# Digital_IO.net
KiCad netlist of a schematic drawn in Altium Designer
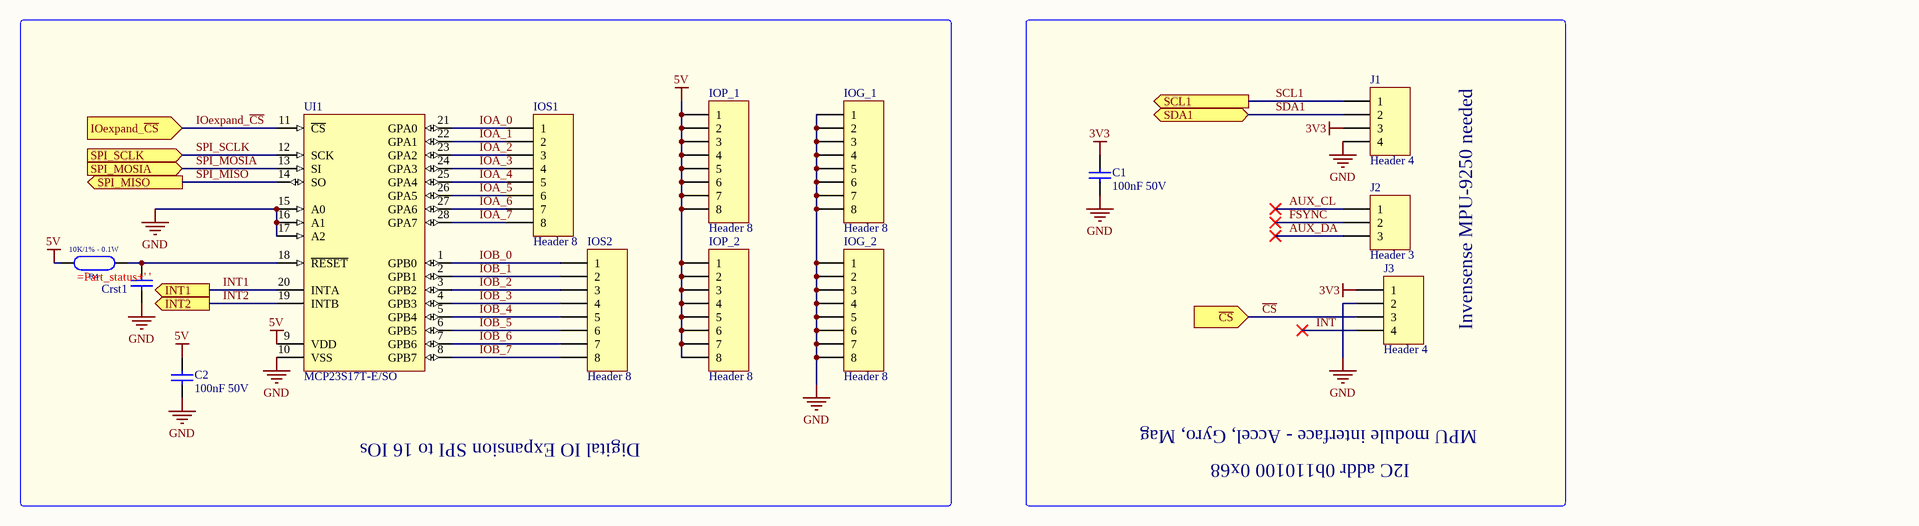
[diagram p0: Digital_IO.SchDoc]

(export (version "E")
  (design (tool "Eeschema 10.0.6"))
  (components
    (comp (ref "C1")
      (value "100nF 50V")
      (footprint "0603C_L")
      (fields
        (field (name "MANUFACTURER") "Yageo")
        (field (name "MANUFACTURER PART NUMBER") "CC0603ZRY5V9BB104")
        (field (name "TOLERANCE") "-20%, +80%")
      )
      (libsource (lib "WCT") (part "Cap101nF_50V_0603"))
    )
    (comp (ref "C2")
      (value "100nF 50V")
      (footprint "0603C_L")
      (fields
        (field (name "MANUFACTURER") "Yageo")
        (field (name "MANUFACTURER PART NUMBER") "CC0603ZRY5V9BB104")
        (field (name "TOLERANCE") "-20%, +80%")
      )
      (libsource (lib "WCT") (part "Cap101nF_50V_0603"))
    )
    (comp (ref "Crst1")
      (value "100nF 50V")
      (footprint "0603C_L")
      (fields
        (field (name "MANUFACTURER") "Yageo")
        (field (name "MANUFACTURER PART NUMBER") "CC0603ZRY5V9BB104")
        (field (name "TOLERANCE") "-20%, +80%")
      )
      (libsource (lib "WCT") (part "Cap100nF_50V_0603"))
    )
    (comp (ref "IOG_1")
      (value "Header 8")
      (footprint "HDR1X8")
      (description "Header, 8-Pin")
      (fields (field (name "PUBLISHER") "Altium Limited"))
      (libsource (lib "Miscellaneous Connectors") (part "Header 8"))
    )
    (comp (ref "IOG_2")
      (value "Header 8")
      (footprint "HDR1X8")
      (description "Header, 8-Pin")
      (fields (field (name "PUBLISHER") "Altium Limited"))
      (libsource (lib "Miscellaneous Connectors") (part "Header 8"))
    )
    (comp (ref "IOP_1")
      (value "Header 8")
      (footprint "HDR1X8")
      (description "Header, 8-Pin")
      (fields (field (name "PUBLISHER") "Altium Limited"))
      (libsource (lib "Miscellaneous Connectors") (part "Header 8"))
    )
    (comp (ref "IOP_2")
      (value "Header 8")
      (footprint "HDR1X8")
      (description "Header, 8-Pin")
      (fields (field (name "PUBLISHER") "Altium Limited"))
      (libsource (lib "Miscellaneous Connectors") (part "Header 8"))
    )
    (comp (ref "IOS1")
      (value "Header 8")
      (footprint "HDR1X8")
      (description "Header, 8-Pin")
      (fields (field (name "PUBLISHER") "Altium Limited"))
      (libsource (lib "Miscellaneous Connectors") (part "Header 8"))
    )
    (comp (ref "IOS2")
      (value "Header 8")
      (footprint "HDR1X8")
      (description "Header, 8-Pin")
      (fields (field (name "PUBLISHER") "Altium Limited"))
      (libsource (lib "Miscellaneous Connectors") (part "Header 8"))
    )
    (comp (ref "J1")
      (value "Header 4")
      (footprint "HDR1X4")
      (description "Header, 4-Pin")
      (fields (field (name "PUBLISHER") "Altium Limited"))
      (libsource (lib "Miscellaneous Connectors") (part "Header 4"))
    )
    (comp (ref "J2")
      (value "Header 3")
      (footprint "HDR1X3")
      (description "Header, 3-Pin")
      (fields (field (name "PUBLISHER") "Altium Limited"))
      (libsource (lib "Miscellaneous Connectors") (part "Header 3"))
    )
    (comp (ref "J3")
      (value "Header 4")
      (footprint "HDR1X4")
      (description "Header, 4-Pin")
      (fields (field (name "PUBLISHER") "Altium Limited"))
      (libsource (lib "Miscellaneous Connectors") (part "Header 4"))
    )
    (comp (ref "R4")
      (value "10K/1% - 0.1W")
      (footprint "R0603")
      (description "Resistor 10K ±1% 0.1W 0603")
      (fields (field (name "TOLERANCE") "±1%") (field (name "POWER") "0.1W"))
      (libsource (lib "EDS_Hardware_gitLIB_Perto") (part "Resistor"))
    )
    (comp (ref "UI1")
      (value "MCP23S17T-E/SO")
      (footprint "SOIC-SO28_L")
      (description "16-Bit I/O Expander with Serial Interface, 28-Pin SOIC, Extended Temperature, Tape and Reel")
      (libsource (lib "Altium Content Vault") (part "CMP-0186-00131-2"))
    )
  )
  (nets
    (net (code "1") (name "/AUX_CL") (class "Default")
      (node (ref "J2") (pin "1") (pinfunction "1_1") (pintype "passive+no_connect"))
    )
    (net (code "2") (name "/AUX_DA") (class "Default")
      (node (ref "J2") (pin "3") (pinfunction "3_3") (pintype "passive+no_connect"))
    )
    (net (code "3") (name "/FSYNC") (class "Default")
      (node (ref "J2") (pin "2") (pinfunction "2_2") (pintype "passive+no_connect"))
    )
    (net (code "4") (name "/INT") (class "Default")
      (node (ref "J3") (pin "4") (pinfunction "4_4") (pintype "passive+no_connect"))
    )
    (net (code "5") (name "/INT1") (class "Default")
      (node (ref "UI1") (pin "20") (pinfunction "INTA_20") (pintype "open_collector"))
    )
    (net (code "6") (name "/INT2") (class "Default")
      (node (ref "UI1") (pin "19") (pinfunction "INTB_19") (pintype "open_collector"))
    )
    (net (code "7") (name "/IOA_0") (class "Default")
      (node (ref "IOS1") (pin "1") (pinfunction "1_1") (pintype "passive"))
      (node (ref "UI1") (pin "21") (pinfunction "GPA0_21") (pintype "bidirectional"))
    )
    (net (code "8") (name "/IOA_1") (class "Default")
      (node (ref "IOS1") (pin "2") (pinfunction "2_2") (pintype "passive"))
      (node (ref "UI1") (pin "22") (pinfunction "GPA1_22") (pintype "bidirectional"))
    )
    (net (code "9") (name "/IOA_2") (class "Default")
      (node (ref "IOS1") (pin "3") (pinfunction "3_3") (pintype "passive"))
      (node (ref "UI1") (pin "23") (pinfunction "GPA2_23") (pintype "bidirectional"))
    )
    (net (code "10") (name "/IOA_3") (class "Default")
      (node (ref "IOS1") (pin "4") (pinfunction "4_4") (pintype "passive"))
      (node (ref "UI1") (pin "24") (pinfunction "GPA3_24") (pintype "bidirectional"))
    )
    (net (code "11") (name "/IOA_4") (class "Default")
      (node (ref "IOS1") (pin "5") (pinfunction "5_5") (pintype "passive"))
      (node (ref "UI1") (pin "25") (pinfunction "GPA4_25") (pintype "bidirectional"))
    )
    (net (code "12") (name "/IOA_5") (class "Default")
      (node (ref "IOS1") (pin "6") (pinfunction "6_6") (pintype "passive"))
      (node (ref "UI1") (pin "26") (pinfunction "GPA5_26") (pintype "bidirectional"))
    )
    (net (code "13") (name "/IOA_6") (class "Default")
      (node (ref "IOS1") (pin "7") (pinfunction "7_7") (pintype "passive"))
      (node (ref "UI1") (pin "27") (pinfunction "GPA6_27") (pintype "bidirectional"))
    )
    (net (code "14") (name "/IOA_7") (class "Default")
      (node (ref "IOS1") (pin "8") (pinfunction "8_8") (pintype "passive"))
      (node (ref "UI1") (pin "28") (pinfunction "GPA7_28") (pintype "bidirectional"))
    )
    (net (code "15") (name "/IOB_0") (class "Default")
      (node (ref "IOS2") (pin "1") (pinfunction "1_1") (pintype "passive"))
      (node (ref "UI1") (pin "1") (pinfunction "GPB0_1") (pintype "bidirectional"))
    )
    (net (code "16") (name "/IOB_1") (class "Default")
      (node (ref "IOS2") (pin "2") (pinfunction "2_2") (pintype "passive"))
      (node (ref "UI1") (pin "2") (pinfunction "GPB1_2") (pintype "bidirectional"))
    )
    (net (code "17") (name "/IOB_2") (class "Default")
      (node (ref "IOS2") (pin "3") (pinfunction "3_3") (pintype "passive"))
      (node (ref "UI1") (pin "3") (pinfunction "GPB2_3") (pintype "bidirectional"))
    )
    (net (code "18") (name "/IOB_3") (class "Default")
      (node (ref "IOS2") (pin "4") (pinfunction "4_4") (pintype "passive"))
      (node (ref "UI1") (pin "4") (pinfunction "GPB3_4") (pintype "bidirectional"))
    )
    (net (code "19") (name "/IOB_4") (class "Default")
      (node (ref "IOS2") (pin "5") (pinfunction "5_5") (pintype "passive"))
      (node (ref "UI1") (pin "5") (pinfunction "GPB4_5") (pintype "bidirectional"))
    )
    (net (code "20") (name "/IOB_5") (class "Default")
      (node (ref "IOS2") (pin "6") (pinfunction "6_6") (pintype "passive"))
      (node (ref "UI1") (pin "6") (pinfunction "GPB5_6") (pintype "bidirectional"))
    )
    (net (code "21") (name "/IOB_6") (class "Default")
      (node (ref "IOS2") (pin "7") (pinfunction "7_7") (pintype "passive"))
      (node (ref "UI1") (pin "7") (pinfunction "GPB6_7") (pintype "bidirectional"))
    )
    (net (code "22") (name "/IOB_7") (class "Default")
      (node (ref "IOS2") (pin "8") (pinfunction "8_8") (pintype "passive"))
      (node (ref "UI1") (pin "8") (pinfunction "GPB7_8") (pintype "bidirectional"))
    )
    (net (code "23") (name "/IOexpand_~{CS}") (class "Default")
      (node (ref "UI1") (pin "11") (pinfunction "~{CS}_11") (pintype "input"))
    )
    (net (code "24") (name "/SCL1") (class "Default")
      (node (ref "J1") (pin "1") (pinfunction "1_1") (pintype "passive"))
    )
    (net (code "25") (name "/SDA1") (class "Default")
      (node (ref "J1") (pin "2") (pinfunction "2_2") (pintype "passive"))
    )
    (net (code "26") (name "/SPI_MISO") (class "Default")
      (node (ref "UI1") (pin "14") (pinfunction "SO_14") (pintype "bidirectional"))
    )
    (net (code "27") (name "/SPI_MOSIA") (class "Default")
      (node (ref "UI1") (pin "13") (pinfunction "SI_13") (pintype "input"))
    )
    (net (code "28") (name "/SPI_SCLK") (class "Default")
      (node (ref "UI1") (pin "12") (pinfunction "SCK_12") (pintype "input"))
    )
    (net (code "29") (name "/~{CS}") (class "Default")
      (node (ref "J3") (pin "3") (pinfunction "3_3") (pintype "passive"))
    )
    (net (code "30") (name "3V3") (class "Default")
      (node (ref "C1") (pin "2") (pinfunction "2_2") (pintype "passive"))
      (node (ref "J1") (pin "3") (pinfunction "3_3") (pintype "passive"))
      (node (ref "J3") (pin "1") (pinfunction "1_1") (pintype "passive"))
    )
    (net (code "31") (name "5V") (class "Default")
      (node (ref "C2") (pin "2") (pinfunction "2_2") (pintype "passive"))
      (node (ref "IOP_1") (pin "1") (pinfunction "1_1") (pintype "passive"))
      (node (ref "IOP_1") (pin "2") (pinfunction "2_2") (pintype "passive"))
      (node (ref "IOP_1") (pin "3") (pinfunction "3_3") (pintype "passive"))
      (node (ref "IOP_1") (pin "4") (pinfunction "4_4") (pintype "passive"))
      (node (ref "IOP_1") (pin "5") (pinfunction "5_5") (pintype "passive"))
      (node (ref "IOP_1") (pin "6") (pinfunction "6_6") (pintype "passive"))
      (node (ref "IOP_1") (pin "7") (pinfunction "7_7") (pintype "passive"))
      (node (ref "IOP_1") (pin "8") (pinfunction "8_8") (pintype "passive"))
      (node (ref "IOP_2") (pin "1") (pinfunction "1_1") (pintype "passive"))
      (node (ref "IOP_2") (pin "2") (pinfunction "2_2") (pintype "passive"))
      (node (ref "IOP_2") (pin "3") (pinfunction "3_3") (pintype "passive"))
      (node (ref "IOP_2") (pin "4") (pinfunction "4_4") (pintype "passive"))
      (node (ref "IOP_2") (pin "5") (pinfunction "5_5") (pintype "passive"))
      (node (ref "IOP_2") (pin "6") (pinfunction "6_6") (pintype "passive"))
      (node (ref "IOP_2") (pin "7") (pinfunction "7_7") (pintype "passive"))
      (node (ref "IOP_2") (pin "8") (pinfunction "8_8") (pintype "passive"))
      (node (ref "R4") (pin "1") (pintype "passive"))
      (node (ref "UI1") (pin "9") (pinfunction "VDD_9") (pintype "power_in"))
    )
    (net (code "32") (name "GND") (class "Default")
      (node (ref "C1") (pin "1") (pinfunction "1_1") (pintype "passive"))
      (node (ref "C2") (pin "1") (pinfunction "1_1") (pintype "passive"))
      (node (ref "Crst1") (pin "1") (pinfunction "1_1") (pintype "passive"))
      (node (ref "IOG_1") (pin "1") (pinfunction "1_1") (pintype "passive"))
      (node (ref "IOG_1") (pin "2") (pinfunction "2_2") (pintype "passive"))
      (node (ref "IOG_1") (pin "3") (pinfunction "3_3") (pintype "passive"))
      (node (ref "IOG_1") (pin "4") (pinfunction "4_4") (pintype "passive"))
      (node (ref "IOG_1") (pin "5") (pinfunction "5_5") (pintype "passive"))
      (node (ref "IOG_1") (pin "6") (pinfunction "6_6") (pintype "passive"))
      (node (ref "IOG_1") (pin "7") (pinfunction "7_7") (pintype "passive"))
      (node (ref "IOG_1") (pin "8") (pinfunction "8_8") (pintype "passive"))
      (node (ref "IOG_2") (pin "1") (pinfunction "1_1") (pintype "passive"))
      (node (ref "IOG_2") (pin "2") (pinfunction "2_2") (pintype "passive"))
      (node (ref "IOG_2") (pin "3") (pinfunction "3_3") (pintype "passive"))
      (node (ref "IOG_2") (pin "4") (pinfunction "4_4") (pintype "passive"))
      (node (ref "IOG_2") (pin "5") (pinfunction "5_5") (pintype "passive"))
      (node (ref "IOG_2") (pin "6") (pinfunction "6_6") (pintype "passive"))
      (node (ref "IOG_2") (pin "7") (pinfunction "7_7") (pintype "passive"))
      (node (ref "IOG_2") (pin "8") (pinfunction "8_8") (pintype "passive"))
      (node (ref "J1") (pin "4") (pinfunction "4_4") (pintype "passive"))
      (node (ref "J3") (pin "2") (pinfunction "2_2") (pintype "passive"))
      (node (ref "UI1") (pin "10") (pinfunction "VSS_10") (pintype "power_in"))
      (node (ref "UI1") (pin "15") (pinfunction "A0_15") (pintype "input"))
      (node (ref "UI1") (pin "16") (pinfunction "A1_16") (pintype "input"))
      (node (ref "UI1") (pin "17") (pinfunction "A2_17") (pintype "input"))
    )
    (net (code "33") (name "Net-(UI1-~{RESET})") (class "Default")
      (node (ref "Crst1") (pin "2") (pinfunction "2_2") (pintype "passive"))
      (node (ref "R4") (pin "2") (pintype "passive"))
      (node (ref "UI1") (pin "18") (pinfunction "~{RESET}_18") (pintype "input"))
    )
  )
)
